# U_Console.net
KiCad netlist of a schematic drawn in Altium Designer
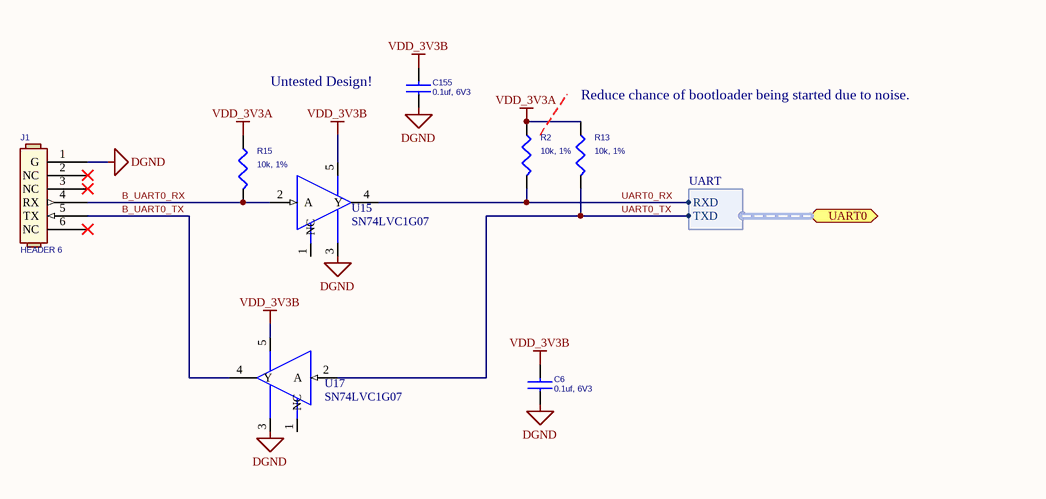
[diagram p0: U_Console.SchDoc]

(export (version "E")
  (design (tool "Eeschema 10.0.6"))
  (components
    (comp (ref "C6")
      (value "0.1uf, 6V3")
      (footprint "402")
      (description "CAP CER 0.1UF 6.3V 10% X5R 0402")
      (fields
        (field (name "MANUFACTURER") "TDK Corporation")
        (field (name "MANUFACTURER PART NUMBER") "C1005X5R0J104K050BA")
      )
      (libsource (lib "BEAGLEBONEBLACK_REV A5B") (part "CAP_0.1uF_X7R_16V_10% 0402"))
    )
    (comp (ref "C155")
      (value "0.1uf, 6V3")
      (footprint "402")
      (description "CAP CER 0.1UF 6.3V 10% X5R 0402")
      (fields
        (field (name "MANUFACTURER") "TDK Corporation")
        (field (name "MANUFACTURER PART NUMBER") "C1005X5R0J104K050BA")
      )
      (libsource (lib "BEAGLEBONEBLACK_REV A5B") (part "CAP_0.1uF_X7R_16V_10% 0402"))
    )
    (comp (ref "J1")
      (value "HEADER 6")
      (footprint "SIP6")
      (description "CONN HEADER 6POS, VERTICAL,  .100 STR TIN")
      (fields
        (field (name "MANUFACTURER") "Samtec Inc")
        (field (name "MANUFACTURER PART NUMBER") "FTR-110-03-G-D-06")
      )
      (libsource (lib "BEAGLEBONEBLACK_REV A5B") (part "HDR_6x1"))
    )
    (comp (ref "R2")
      (value "10k, 1%")
      (footprint "402")
      (description "RES 10K OHM 1/16W 5% 0402 SMD")
      (fields
        (field (name "MANUFACTURER") "Rohm Semiconductor")
        (field (name "MANUFACTURER PART NUMBER") "MCR01MZPJ103")
      )
      (libsource (lib "BEAGLEBONEBLACK_REV A5B") (part "RES_10K_1/16W_1%_0402"))
    )
    (comp (ref "R13")
      (value "10k, 1%")
      (footprint "402")
      (description "RES 10K OHM 1/16W 5% 0402 SMD")
      (fields
        (field (name "MANUFACTURER") "Rohm Semiconductor")
        (field (name "MANUFACTURER PART NUMBER") "MCR01MZPJ103")
      )
      (libsource (lib "BEAGLEBONEBLACK_REV A5B") (part "RES_10K_1/16W_1%_0402"))
    )
    (comp (ref "R15")
      (value "10k, 1%")
      (footprint "402")
      (description "RES 10K OHM 1/16W 5% 0402 SMD")
      (fields
        (field (name "MANUFACTURER") "Rohm Semiconductor")
        (field (name "MANUFACTURER PART NUMBER") "MCR01MZPJ103")
      )
      (libsource (lib "BEAGLEBONEBLACK_REV A5B") (part "RES_10K_1/16W_1%_0402"))
    )
    (comp (ref "U15")
      (value "SN74LVC1G07")
      (footprint "DCK5_2P15X1P4")
      (description "IC BUFFER SINGLE 1INPUT SC705")
      (fields
        (field (name "MANUFACTURER") "Texas Instruments")
        (field (name "MANUFACTURER PART NUMBER") "SN74LVC1G06DCKTG4")
      )
      (libsource (lib "BEAGLEBONEBLACK_REV A5B_1") (part "SN74LVC1G07DCK"))
    )
    (comp (ref "U17")
      (value "SN74LVC1G07")
      (footprint "DCK5_2P15X1P4")
      (description "IC BUFFER SINGLE 1INPUT SC705")
      (fields
        (field (name "MANUFACTURER") "Texas Instruments")
        (field (name "MANUFACTURER PART NUMBER") "SN74LVC1G06DCKTG4")
      )
      (libsource (lib "BEAGLEBONEBLACK_REV A5B_1") (part "SN74LVC1G07DCK"))
    )
  )
  (nets
    (net (code "2") (name "/B_UART0_RX") (class "Default")
      (node (ref "J1") (pin "4") (pinfunction "RX_4") (pintype "output"))
      (node (ref "R15") (pin "2") (pinfunction "2_2") (pintype "passive"))
      (node (ref "U15") (pin "2") (pinfunction "A_2") (pintype "input"))
    )
    (net (code "3") (name "/B_UART0_TX") (class "Default")
      (node (ref "J1") (pin "5") (pinfunction "TX_5") (pintype "input"))
      (node (ref "U17") (pin "4") (pinfunction "Y_4") (pintype "open_collector"))
    )
    (net (code "4") (name "/UART0_RX") (class "Default")
      (node (ref "R2") (pin "2") (pinfunction "2_2") (pintype "passive"))
      (node (ref "U15") (pin "4") (pinfunction "Y_4") (pintype "open_collector"))
    )
    (net (code "5") (name "/UART0_TX") (class "Default")
      (node (ref "R13") (pin "2") (pinfunction "2_2") (pintype "passive"))
      (node (ref "U17") (pin "2") (pinfunction "A_2") (pintype "input"))
    )
    (net (code "7") (name "DGND") (class "Default")
      (node (ref "C155") (pin "1") (pinfunction "1_1") (pintype "passive"))
      (node (ref "C6") (pin "1") (pinfunction "1_1") (pintype "passive"))
      (node (ref "J1") (pin "1") (pinfunction "G_1") (pintype "power_in"))
      (node (ref "U15") (pin "3") (pinfunction "GND_3") (pintype "power_in"))
      (node (ref "U17") (pin "3") (pinfunction "GND_3") (pintype "power_in"))
    )
    (net (code "8") (name "VDD_3V3A") (class "Default")
      (node (ref "R13") (pin "1") (pinfunction "1_1") (pintype "passive"))
      (node (ref "R15") (pin "1") (pinfunction "1_1") (pintype "passive"))
      (node (ref "R2") (pin "1") (pinfunction "1_1") (pintype "passive"))
    )
    (net (code "9") (name "VDD_3V3B") (class "Default")
      (node (ref "C155") (pin "2") (pinfunction "2_2") (pintype "passive"))
      (node (ref "C6") (pin "2") (pinfunction "2_2") (pintype "passive"))
      (node (ref "U15") (pin "5") (pinfunction "VCC_5") (pintype "power_in"))
      (node (ref "U17") (pin "5") (pinfunction "VCC_5") (pintype "power_in"))
    )
    (net (code "10") (name "unconnected-(J1-NC-Pad2)") (class "Default")
      (node (ref "J1") (pin "2") (pinfunction "NC_2") (pintype "passive+no_connect"))
    )
    (net (code "11") (name "unconnected-(J1-NC-Pad3)") (class "Default")
      (node (ref "J1") (pin "3") (pinfunction "NC_3") (pintype "passive+no_connect"))
    )
    (net (code "12") (name "unconnected-(J1-NC-Pad6)") (class "Default")
      (node (ref "J1") (pin "6") (pinfunction "NC_6") (pintype "passive+no_connect"))
    )
    (net (code "13") (name "unconnected-(U15-NC-Pad1)") (class "Default")
      (node (ref "U15") (pin "1") (pinfunction "NC_1") (pintype "passive"))
    )
    (net (code "14") (name "unconnected-(U17-NC-Pad1)") (class "Default")
      (node (ref "U17") (pin "1") (pinfunction "NC_1") (pintype "passive"))
    )
  )
)
